# MainDevice.net
KiCad netlist of a schematic drawn in EAGLE
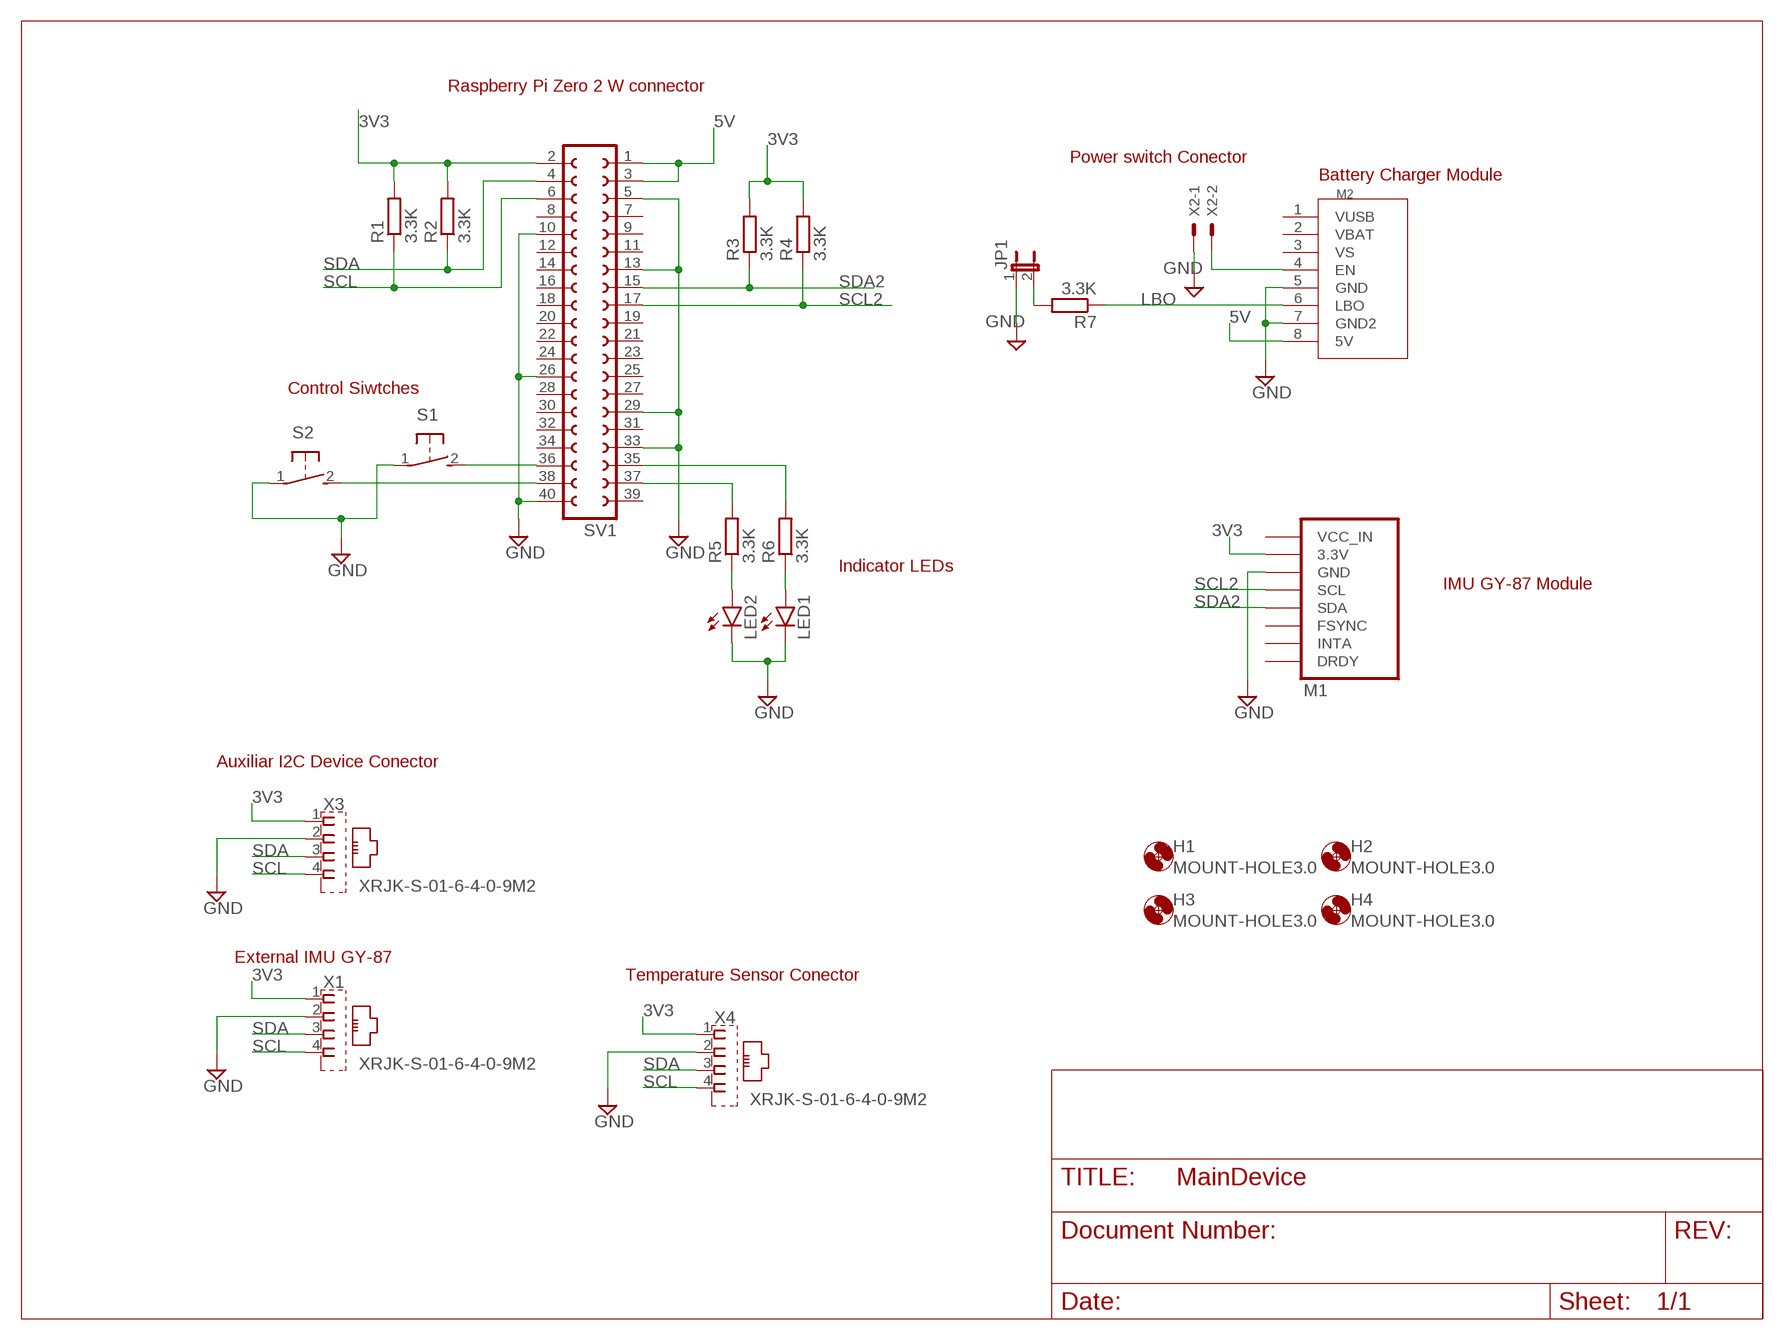
[diagram p0: schematic, sheet 1]

(export (version "E")
  (design (tool "Eeschema 10.0.6"))
  (components
    (comp (ref "H1")
      (value "MOUNT-HOLE3.0")
      (footprint "eagle-import:3,0")
      (libsource (lib "eagle-import") (part "MOUNT-HOLE3.0"))
    )
    (comp (ref "H2")
      (value "MOUNT-HOLE3.0")
      (footprint "eagle-import:3,0")
      (libsource (lib "eagle-import") (part "MOUNT-HOLE3.0"))
    )
    (comp (ref "H3")
      (value "MOUNT-HOLE3.0")
      (footprint "eagle-import:3,0")
      (libsource (lib "eagle-import") (part "MOUNT-HOLE3.0"))
    )
    (comp (ref "H4")
      (value "MOUNT-HOLE3.0")
      (footprint "eagle-import:3,0")
      (libsource (lib "eagle-import") (part "MOUNT-HOLE3.0"))
    )
    (comp (ref "JP1")
      (value "JP1E")
      (footprint "eagle-import:JP1")
      (libsource (lib "eagle-import") (part "JP1E"))
    )
    (comp (ref "LED1")
      (value "LED5MM")
      (footprint "eagle-import:LED5MM")
      (libsource (lib "eagle-import") (part "LED5MM"))
    )
    (comp (ref "LED2")
      (value "LED5MM")
      (footprint "eagle-import:LED5MM")
      (libsource (lib "eagle-import") (part "LED5MM"))
    )
    (comp (ref "M1")
      (value "GY-87")
      (footprint "eagle-import:GY-87")
      (libsource (lib "eagle-import") (part "GY-87"))
    )
    (comp (ref "M2")
      (value "POWERBOOST_1000C")
      (footprint "eagle-import:POWERBOOST_1000C")
      (libsource (lib "eagle-import") (part "POWERBOOST_1000C"))
    )
    (comp (ref "R1")
      (value "3.3K")
      (footprint "eagle-import:R0805")
      (libsource (lib "eagle-import") (part "R-EU_R0805"))
    )
    (comp (ref "R2")
      (value "3.3K")
      (footprint "eagle-import:R0805")
      (libsource (lib "eagle-import") (part "R-EU_R0805"))
    )
    (comp (ref "R3")
      (value "3.3K")
      (footprint "eagle-import:R0805")
      (libsource (lib "eagle-import") (part "R-EU_R0805"))
    )
    (comp (ref "R4")
      (value "3.3K")
      (footprint "eagle-import:R0805")
      (libsource (lib "eagle-import") (part "R-EU_R0805"))
    )
    (comp (ref "R5")
      (value "3.3K")
      (footprint "eagle-import:R0805")
      (libsource (lib "eagle-import") (part "R-EU_R0805"))
    )
    (comp (ref "R6")
      (value "3.3K")
      (footprint "eagle-import:R0805")
      (libsource (lib "eagle-import") (part "R-EU_R0805"))
    )
    (comp (ref "R7")
      (value "3.3K")
      (footprint "eagle-import:R0805")
      (libsource (lib "eagle-import") (part "R-EU_R0805"))
    )
    (comp (ref "S1")
      (value "31-XX")
      (footprint "eagle-import:B3F-31XX")
      (fields (field (name "MPN") "B3F-3100"))
      (libsource (lib "eagle-import") (part "31-XX"))
    )
    (comp (ref "S2")
      (value "31-XX")
      (footprint "eagle-import:B3F-31XX")
      (fields (field (name "MPN") "B3F-3100"))
      (libsource (lib "eagle-import") (part "31-XX"))
    )
    (comp (ref "SV1")
      (value "FE20-2")
      (footprint "eagle-import:FE20-2")
      (libsource (lib "eagle-import") (part "FE20-2"))
    )
    (comp (ref "X1")
      (value "XRJK-S-01-6-4-0-9M2")
      (footprint "eagle-import:XRJK-S-01-6-4-0-9M2")
      (libsource (lib "eagle-import") (part "XRJK4-0-9M2-S-01-6-"))
    )
    (comp (ref "X2")
      (value "22-23-2021")
      (footprint "eagle-import:22-23-2021")
      (fields (field (name "MF") "MOLEX"))
      (libsource (lib "eagle-import") (part "22-23-2021"))
    )
    (comp (ref "X3")
      (value "XRJK-S-01-6-4-0-9M2")
      (footprint "eagle-import:XRJK-S-01-6-4-0-9M2")
      (libsource (lib "eagle-import") (part "XRJK4-0-9M2-S-01-6-"))
    )
    (comp (ref "X4")
      (value "XRJK-S-01-6-4-0-9M2")
      (footprint "eagle-import:XRJK-S-01-6-4-0-9M2")
      (libsource (lib "eagle-import") (part "XRJK4-0-9M2-S-01-6-"))
    )
  )
  (nets
    (net (code "1") (name "/3V3") (class "Default")
      (node (ref "M1") (pin "2") (pinfunction "3.3V_2") (pintype "passive"))
      (node (ref "R1") (pin "2") (pinfunction "2_2") (pintype "passive"))
      (node (ref "R2") (pin "2") (pinfunction "2_2") (pintype "passive"))
      (node (ref "R3") (pin "2") (pinfunction "2_2") (pintype "passive"))
      (node (ref "R4") (pin "2") (pinfunction "2_2") (pintype "passive"))
      (node (ref "SV1") (pin "2") (pinfunction "2_2") (pintype "passive"))
      (node (ref "X1") (pin "1") (pinfunction "1_1") (pintype "passive"))
      (node (ref "X3") (pin "1") (pinfunction "1_1") (pintype "passive"))
      (node (ref "X4") (pin "1") (pinfunction "1_1") (pintype "passive"))
    )
    (net (code "2") (name "/5V") (class "Default")
      (node (ref "M2") (pin "8") (pinfunction "5V_8") (pintype "bidirectional"))
      (node (ref "SV1") (pin "1") (pinfunction "1_1") (pintype "passive"))
      (node (ref "SV1") (pin "3") (pinfunction "3_3") (pintype "passive"))
    )
    (net (code "3") (name "/LBO") (class "Default")
      (node (ref "M2") (pin "6") (pinfunction "LBO_6") (pintype "bidirectional"))
      (node (ref "R7") (pin "1") (pinfunction "1_1") (pintype "passive"))
    )
    (net (code "4") (name "/SCL") (class "Default")
      (node (ref "R1") (pin "1") (pinfunction "1_1") (pintype "passive"))
      (node (ref "SV1") (pin "6") (pinfunction "6_6") (pintype "passive"))
      (node (ref "X1") (pin "4") (pinfunction "4_4") (pintype "passive"))
      (node (ref "X3") (pin "4") (pinfunction "4_4") (pintype "passive"))
      (node (ref "X4") (pin "4") (pinfunction "4_4") (pintype "passive"))
    )
    (net (code "5") (name "/SCL2") (class "Default")
      (node (ref "M1") (pin "4") (pinfunction "SCL_4") (pintype "passive"))
      (node (ref "R4") (pin "1") (pinfunction "1_1") (pintype "passive"))
      (node (ref "SV1") (pin "17") (pinfunction "17_17") (pintype "passive"))
    )
    (net (code "6") (name "/SDA") (class "Default")
      (node (ref "R2") (pin "1") (pinfunction "1_1") (pintype "passive"))
      (node (ref "SV1") (pin "4") (pinfunction "4_4") (pintype "passive"))
      (node (ref "X1") (pin "3") (pinfunction "3_3") (pintype "passive"))
      (node (ref "X3") (pin "3") (pinfunction "3_3") (pintype "passive"))
      (node (ref "X4") (pin "3") (pinfunction "3_3") (pintype "passive"))
    )
    (net (code "7") (name "/SDA2") (class "Default")
      (node (ref "M1") (pin "5") (pinfunction "SDA_5") (pintype "passive"))
      (node (ref "R3") (pin "1") (pinfunction "1_1") (pintype "passive"))
      (node (ref "SV1") (pin "15") (pinfunction "15_15") (pintype "passive"))
    )
    (net (code "8") (name "GND") (class "Default")
      (node (ref "JP1") (pin "1") (pinfunction "1_1") (pintype "passive"))
      (node (ref "LED1") (pin "K") (pinfunction "C_K") (pintype "passive"))
      (node (ref "LED2") (pin "K") (pinfunction "C_K") (pintype "passive"))
      (node (ref "M1") (pin "3") (pinfunction "GND_3") (pintype "passive"))
      (node (ref "M2") (pin "5") (pinfunction "GND_5") (pintype "bidirectional"))
      (node (ref "M2") (pin "7") (pinfunction "GND2_7") (pintype "bidirectional"))
      (node (ref "S1") (pin "1") (pinfunction "P_1") (pintype "passive"))
      (node (ref "S2") (pin "1") (pinfunction "P_1") (pintype "passive"))
      (node (ref "SV1") (pin "10") (pinfunction "10_10") (pintype "passive"))
      (node (ref "SV1") (pin "13") (pinfunction "13_13") (pintype "passive"))
      (node (ref "SV1") (pin "26") (pinfunction "26_26") (pintype "passive"))
      (node (ref "SV1") (pin "29") (pinfunction "29_29") (pintype "passive"))
      (node (ref "SV1") (pin "33") (pinfunction "33_33") (pintype "passive"))
      (node (ref "SV1") (pin "40") (pinfunction "40_40") (pintype "passive"))
      (node (ref "SV1") (pin "5") (pinfunction "5_5") (pintype "passive"))
      (node (ref "X1") (pin "2") (pinfunction "2_2") (pintype "passive"))
      (node (ref "X2") (pin "1") (pinfunction "S_1") (pintype "passive"))
      (node (ref "X3") (pin "2") (pinfunction "2_2") (pintype "passive"))
      (node (ref "X4") (pin "2") (pinfunction "2_2") (pintype "passive"))
    )
    (net (code "9") (name "Net-(JP1-Pad2)") (class "Default")
      (node (ref "JP1") (pin "2") (pinfunction "2_2") (pintype "passive"))
      (node (ref "R7") (pin "2") (pinfunction "2_2") (pintype "passive"))
    )
    (net (code "10") (name "Net-(LED1-PadA)") (class "Default")
      (node (ref "LED1") (pin "A") (pinfunction "A_A") (pintype "passive"))
      (node (ref "R6") (pin "1") (pinfunction "1_1") (pintype "passive"))
    )
    (net (code "11") (name "Net-(LED2-PadA)") (class "Default")
      (node (ref "LED2") (pin "A") (pinfunction "A_A") (pintype "passive"))
      (node (ref "R5") (pin "1") (pinfunction "1_1") (pintype "passive"))
    )
    (net (code "12") (name "Net-(M2-EN)") (class "Default")
      (node (ref "M2") (pin "4") (pinfunction "EN_4") (pintype "bidirectional"))
      (node (ref "X2") (pin "2") (pinfunction "S_2") (pintype "passive"))
    )
    (net (code "13") (name "Net-(R5-Pad2)") (class "Default")
      (node (ref "R5") (pin "2") (pinfunction "2_2") (pintype "passive"))
      (node (ref "SV1") (pin "37") (pinfunction "37_37") (pintype "passive"))
    )
    (net (code "14") (name "Net-(R6-Pad2)") (class "Default")
      (node (ref "R6") (pin "2") (pinfunction "2_2") (pintype "passive"))
      (node (ref "SV1") (pin "35") (pinfunction "35_35") (pintype "passive"))
    )
    (net (code "15") (name "Net-(S1-S)") (class "Default")
      (node (ref "S1") (pin "2") (pinfunction "S_2") (pintype "passive"))
      (node (ref "SV1") (pin "36") (pinfunction "36_36") (pintype "passive"))
    )
    (net (code "16") (name "Net-(S2-S)") (class "Default")
      (node (ref "S2") (pin "2") (pinfunction "S_2") (pintype "passive"))
      (node (ref "SV1") (pin "38") (pinfunction "38_38") (pintype "passive"))
    )
    (net (code "17") (name "unconnected-(M1-DRDY-Pad8)") (class "Default")
      (node (ref "M1") (pin "8") (pinfunction "DRDY_8") (pintype "passive"))
    )
    (net (code "18") (name "unconnected-(M1-FSYNC-Pad6)") (class "Default")
      (node (ref "M1") (pin "6") (pinfunction "FSYNC_6") (pintype "passive"))
    )
    (net (code "19") (name "unconnected-(M1-INTA-Pad7)") (class "Default")
      (node (ref "M1") (pin "7") (pinfunction "INTA_7") (pintype "passive"))
    )
    (net (code "20") (name "unconnected-(M1-VCC_IN-Pad1)") (class "Default")
      (node (ref "M1") (pin "1") (pinfunction "VCC_IN_1") (pintype "passive"))
    )
    (net (code "21") (name "unconnected-(M2-VBAT-Pad2)") (class "Default")
      (node (ref "M2") (pin "2") (pinfunction "VBAT_2") (pintype "bidirectional"))
    )
    (net (code "22") (name "unconnected-(M2-VS-Pad3)") (class "Default")
      (node (ref "M2") (pin "3") (pinfunction "VS_3") (pintype "bidirectional"))
    )
    (net (code "23") (name "unconnected-(M2-VUSB-Pad1)") (class "Default")
      (node (ref "M2") (pin "1") (pinfunction "VUSB_1") (pintype "bidirectional"))
    )
    (net (code "24") (name "unconnected-(SV1-Pad7)") (class "Default")
      (node (ref "SV1") (pin "7") (pinfunction "7_7") (pintype "passive"))
    )
    (net (code "25") (name "unconnected-(SV1-Pad8)") (class "Default")
      (node (ref "SV1") (pin "8") (pinfunction "8_8") (pintype "passive"))
    )
    (net (code "26") (name "unconnected-(SV1-Pad9)") (class "Default")
      (node (ref "SV1") (pin "9") (pinfunction "9_9") (pintype "passive"))
    )
    (net (code "27") (name "unconnected-(SV1-Pad11)") (class "Default")
      (node (ref "SV1") (pin "11") (pinfunction "11_11") (pintype "passive"))
    )
    (net (code "28") (name "unconnected-(SV1-Pad12)") (class "Default")
      (node (ref "SV1") (pin "12") (pinfunction "12_12") (pintype "passive"))
    )
    (net (code "29") (name "unconnected-(SV1-Pad14)") (class "Default")
      (node (ref "SV1") (pin "14") (pinfunction "14_14") (pintype "passive"))
    )
    (net (code "30") (name "unconnected-(SV1-Pad16)") (class "Default")
      (node (ref "SV1") (pin "16") (pinfunction "16_16") (pintype "passive"))
    )
    (net (code "31") (name "unconnected-(SV1-Pad18)") (class "Default")
      (node (ref "SV1") (pin "18") (pinfunction "18_18") (pintype "passive"))
    )
    (net (code "32") (name "unconnected-(SV1-Pad19)") (class "Default")
      (node (ref "SV1") (pin "19") (pinfunction "19_19") (pintype "passive"))
    )
    (net (code "33") (name "unconnected-(SV1-Pad20)") (class "Default")
      (node (ref "SV1") (pin "20") (pinfunction "20_20") (pintype "passive"))
    )
    (net (code "34") (name "unconnected-(SV1-Pad21)") (class "Default")
      (node (ref "SV1") (pin "21") (pinfunction "21_21") (pintype "passive"))
    )
    (net (code "35") (name "unconnected-(SV1-Pad22)") (class "Default")
      (node (ref "SV1") (pin "22") (pinfunction "22_22") (pintype "passive"))
    )
    (net (code "36") (name "unconnected-(SV1-Pad23)") (class "Default")
      (node (ref "SV1") (pin "23") (pinfunction "23_23") (pintype "passive"))
    )
    (net (code "37") (name "unconnected-(SV1-Pad24)") (class "Default")
      (node (ref "SV1") (pin "24") (pinfunction "24_24") (pintype "passive"))
    )
    (net (code "38") (name "unconnected-(SV1-Pad25)") (class "Default")
      (node (ref "SV1") (pin "25") (pinfunction "25_25") (pintype "passive"))
    )
    (net (code "39") (name "unconnected-(SV1-Pad27)") (class "Default")
      (node (ref "SV1") (pin "27") (pinfunction "27_27") (pintype "passive"))
    )
    (net (code "40") (name "unconnected-(SV1-Pad28)") (class "Default")
      (node (ref "SV1") (pin "28") (pinfunction "28_28") (pintype "passive"))
    )
    (net (code "41") (name "unconnected-(SV1-Pad30)") (class "Default")
      (node (ref "SV1") (pin "30") (pinfunction "30_30") (pintype "passive"))
    )
    (net (code "42") (name "unconnected-(SV1-Pad31)") (class "Default")
      (node (ref "SV1") (pin "31") (pinfunction "31_31") (pintype "passive"))
    )
    (net (code "43") (name "unconnected-(SV1-Pad32)") (class "Default")
      (node (ref "SV1") (pin "32") (pinfunction "32_32") (pintype "passive"))
    )
    (net (code "44") (name "unconnected-(SV1-Pad34)") (class "Default")
      (node (ref "SV1") (pin "34") (pinfunction "34_34") (pintype "passive"))
    )
    (net (code "45") (name "unconnected-(SV1-Pad39)") (class "Default")
      (node (ref "SV1") (pin "39") (pinfunction "39_39") (pintype "passive"))
    )
  )
)
